# Tube_Screamer_Schematic.net
KiCad netlist of a schematic drawn in EAGLE
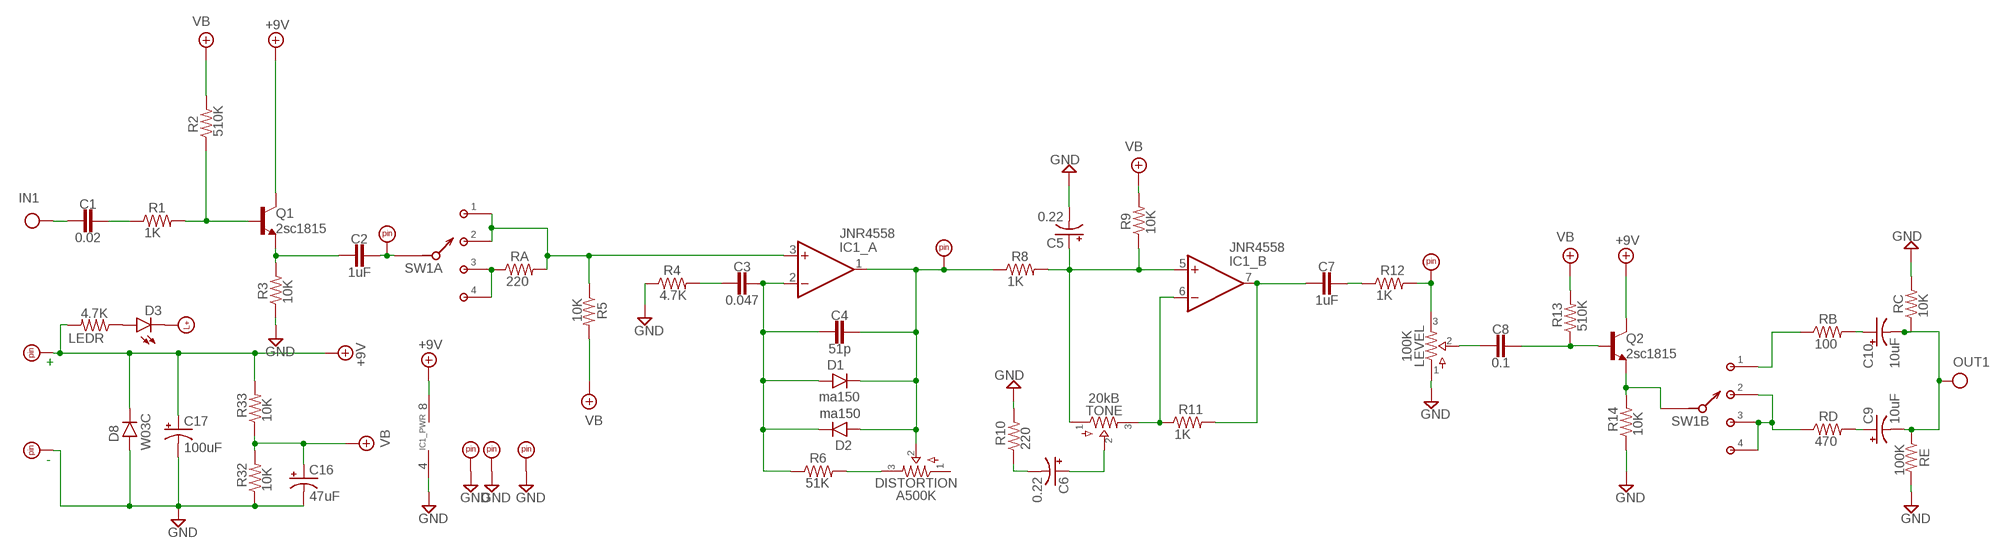
[diagram p0: schematic, sheet 1]

(export (version "E")
  (design (tool "Eeschema 10.0.6"))
  (components
    (comp (ref "C1")
      (value "0.02")
      (footprint "eagle-import:0.2_.MED")
      (libsource (lib "eagle-import") (part "CAP.3"))
    )
    (comp (ref "C2")
      (value "1uF")
      (footprint "eagle-import:0.2_.LRG")
      (libsource (lib "eagle-import") (part "CAP.4"))
    )
    (comp (ref "C3")
      (value "0.047")
      (footprint "eagle-import:0.2_.MED")
      (libsource (lib "eagle-import") (part "CAP.3"))
    )
    (comp (ref "C4")
      (value "51p")
      (footprint "eagle-import:0.2_.MED")
      (libsource (lib "eagle-import") (part "CAP.3"))
    )
    (comp (ref "C5")
      (value "0.22")
      (footprint "eagle-import:050_020_1")
      (libsource (lib "eagle-import") (part "0501"))
    )
    (comp (ref "C6")
      (value "0.22")
      (footprint "eagle-import:050_020_1")
      (libsource (lib "eagle-import") (part "0501"))
    )
    (comp (ref "C7")
      (value "1uF")
      (footprint "eagle-import:0.2_.LRG")
      (libsource (lib "eagle-import") (part "CAP.4"))
    )
    (comp (ref "C8")
      (value "0.1")
      (footprint "eagle-import:0.2_.MED")
      (libsource (lib "eagle-import") (part "CAP.3"))
    )
    (comp (ref "C9")
      (value "10uF")
      (footprint "eagle-import:050_020_1")
      (libsource (lib "eagle-import") (part "0501"))
    )
    (comp (ref "C10")
      (value "10uF")
      (footprint "eagle-import:050_020_1")
      (libsource (lib "eagle-import") (part "0501"))
    )
    (comp (ref "C16")
      (value "47uF")
      (footprint "eagle-import:050_020_1")
      (libsource (lib "eagle-import") (part "0501"))
    )
    (comp (ref "C17")
      (value "100uF")
      (footprint "eagle-import:050_020_1")
      (libsource (lib "eagle-import") (part "0501"))
    )
    (comp (ref "D1")
      (value "ma150")
      (footprint "eagle-import:DO41-3")
      (libsource (lib "eagle-import") (part "DO41.3"))
    )
    (comp (ref "D2")
      (value "ma150")
      (footprint "eagle-import:DO41-3")
      (libsource (lib "eagle-import") (part "DO41.3"))
    )
    (comp (ref "D3")
      (value "LED3MM")
      (footprint "eagle-import:LED3MM")
      (libsource (lib "eagle-import") (part "LED3MM"))
    )
    (comp (ref "D8")
      (value "W03C")
      (footprint "eagle-import:DO35-3")
      (libsource (lib "eagle-import") (part "DO35.3"))
    )
    (comp (ref "DISTORTION")
      (value "A500K")
      (footprint "eagle-import:16MM_B.MOUNT")
      (libsource (lib "eagle-import") (part "16MM.1"))
    )
    (comp (ref "IC1")
      (value "JNR4558")
      (footprint "eagle-import:DIL08")
      (libsource (lib "eagle-import") (part "DUALTH"))
    )
    (comp (ref "IN1")
      (value "IN")
      (footprint "eagle-import:SQUARE")
      (libsource (lib "eagle-import") (part "IN"))
    )
    (comp (ref "LEDR")
      (value "4.7K")
      (footprint "eagle-import:R0207_3")
      (libsource (lib "eagle-import") (part "RESISTORS.3B"))
    )
    (comp (ref "LEVEL")
      (value "100K")
      (footprint "eagle-import:16MM_B.MOUNT")
      (libsource (lib "eagle-import") (part "16MM.1"))
    )
    (comp (ref "OUT1")
      (value "OUT")
      (footprint "eagle-import:SQUARE")
      (libsource (lib "eagle-import") (part "OUT"))
    )
    (comp (ref "Q1")
      (value "2sc1815")
      (footprint "eagle-import:TO92")
      (libsource (lib "eagle-import") (part "2SC945"))
    )
    (comp (ref "Q2")
      (value "2sc1815")
      (footprint "eagle-import:TO92")
      (libsource (lib "eagle-import") (part "2SC945"))
    )
    (comp (ref "R1")
      (value "1K")
      (footprint "eagle-import:R0207_3")
      (libsource (lib "eagle-import") (part "RESISTORS.3B"))
    )
    (comp (ref "R2")
      (value "510K")
      (footprint "eagle-import:R0207_3")
      (libsource (lib "eagle-import") (part "RESISTORS.3B"))
    )
    (comp (ref "R3")
      (value "10K")
      (footprint "eagle-import:R0207_3")
      (libsource (lib "eagle-import") (part "RESISTORS.3B"))
    )
    (comp (ref "R4")
      (value "4.7K")
      (footprint "eagle-import:R0207_3")
      (libsource (lib "eagle-import") (part "RESISTORS.3B"))
    )
    (comp (ref "R5")
      (value "10K")
      (footprint "eagle-import:R0207_3")
      (libsource (lib "eagle-import") (part "RESISTORS.3B"))
    )
    (comp (ref "R6")
      (value "51K")
      (footprint "eagle-import:R0207_3")
      (libsource (lib "eagle-import") (part "RESISTORS.3B"))
    )
    (comp (ref "R8")
      (value "1K")
      (footprint "eagle-import:R0207_3")
      (libsource (lib "eagle-import") (part "RESISTORS.3B"))
    )
    (comp (ref "R9")
      (value "10K")
      (footprint "eagle-import:R0207_3")
      (libsource (lib "eagle-import") (part "RESISTORS.3B"))
    )
    (comp (ref "R10")
      (value "220")
      (footprint "eagle-import:R0207_3")
      (libsource (lib "eagle-import") (part "RESISTORS.3B"))
    )
    (comp (ref "R11")
      (value "1K")
      (footprint "eagle-import:R0207_3")
      (libsource (lib "eagle-import") (part "RESISTORS.3B"))
    )
    (comp (ref "R12")
      (value "1K")
      (footprint "eagle-import:R0207_3")
      (libsource (lib "eagle-import") (part "RESISTORS.3B"))
    )
    (comp (ref "R13")
      (value "510K")
      (footprint "eagle-import:R0207_3")
      (libsource (lib "eagle-import") (part "RESISTORS.3B"))
    )
    (comp (ref "R14")
      (value "10K")
      (footprint "eagle-import:R0207_3")
      (libsource (lib "eagle-import") (part "RESISTORS.3B"))
    )
    (comp (ref "R32")
      (value "10K")
      (footprint "eagle-import:R0207_3")
      (libsource (lib "eagle-import") (part "RESISTORS.3B"))
    )
    (comp (ref "R33")
      (value "10K")
      (footprint "eagle-import:R0207_3")
      (libsource (lib "eagle-import") (part "RESISTORS.3B"))
    )
    (comp (ref "RA")
      (value "220")
      (footprint "eagle-import:R0207_3")
      (libsource (lib "eagle-import") (part "RESISTORS.3B"))
    )
    (comp (ref "RB")
      (value "100")
      (footprint "eagle-import:R0207_3")
      (libsource (lib "eagle-import") (part "RESISTORS.3B"))
    )
    (comp (ref "RC")
      (value "10K")
      (footprint "eagle-import:R0207_3")
      (libsource (lib "eagle-import") (part "RESISTORS.3B"))
    )
    (comp (ref "RD")
      (value "470")
      (footprint "eagle-import:R0207_3")
      (libsource (lib "eagle-import") (part "RESISTORS.3B"))
    )
    (comp (ref "RE")
      (value "100K")
      (footprint "eagle-import:R0207_3")
      (libsource (lib "eagle-import") (part "RESISTORS.3B"))
    )
    (comp (ref "SW1")
      (value "2P4TMINIROTARY")
      (footprint "eagle-import:2P4T.MINI")
      (libsource (lib "eagle-import") (part "2P4TMINIROTARY"))
    )
    (comp (ref "TONE")
      (value "20kB")
      (footprint "eagle-import:16MM_B.MOUNT")
      (libsource (lib "eagle-import") (part "16MM.1"))
    )
    (comp (ref "U$1")
      (value "PADS.RND_NL")
      (footprint "eagle-import:PAD2")
      (libsource (lib "eagle-import") (part "PADS.RND_NL"))
    )
    (comp (ref "U$2")
      (value "PADS.RND_NL")
      (footprint "eagle-import:PAD2")
      (libsource (lib "eagle-import") (part "PADS.RND_NL"))
    )
    (comp (ref "U$3")
      (value "PADS.RND_NL")
      (footprint "eagle-import:PAD2")
      (libsource (lib "eagle-import") (part "PADS.RND_NL"))
    )
    (comp (ref "U$4")
      (value "PADS.RND_NL")
      (footprint "eagle-import:PAD2")
      (libsource (lib "eagle-import") (part "PADS.RND_NL"))
    )
    (comp (ref "U$5")
      (value "PADS.RND_NL")
      (footprint "eagle-import:PAD2")
      (libsource (lib "eagle-import") (part "PADS.RND_NL"))
    )
    (comp (ref "U$6")
      (value "PADS.RND_NL")
      (footprint "eagle-import:PAD2")
      (libsource (lib "eagle-import") (part "PADS.RND_NL"))
    )
    (comp (ref "U$7")
      (value "LED+")
      (footprint "eagle-import:SQUARE")
      (libsource (lib "eagle-import") (part "LED+"))
    )
    (comp (ref "U$8")
      (value "PADS.RND_NL")
      (footprint "eagle-import:PAD2")
      (libsource (lib "eagle-import") (part "PADS.RND_NL"))
    )
    (comp (ref "U$9")
      (value "PADS.RND_NL")
      (footprint "eagle-import:PAD2")
      (libsource (lib "eagle-import") (part "PADS.RND_NL"))
    )
  )
  (nets
    (net (code "1") (name "+9V") (class "Default")
      (node (ref "C17") (pin "+") (pinfunction "+_+") (pintype "passive"))
      (node (ref "D8") (pin "C") (pinfunction "C_C") (pintype "passive"))
      (node (ref "IC1") (pin "8") (pinfunction "V+_8") (pintype "power_in"))
      (node (ref "LEDR") (pin "2") (pinfunction "2_2") (pintype "passive"))
      (node (ref "Q1") (pin "2") (pinfunction "C_2") (pintype "passive"))
      (node (ref "Q2") (pin "2") (pinfunction "C_2") (pintype "passive"))
      (node (ref "R33") (pin "2") (pinfunction "2_2") (pintype "passive"))
      (node (ref "U$1") (pin "P$1") (pinfunction "P$1_P$1") (pintype "bidirectional"))
    )
    (net (code "2") (name "GND") (class "Default")
      (node (ref "C16") (pin "-") (pinfunction "-_-") (pintype "passive"))
      (node (ref "C17") (pin "-") (pinfunction "-_-") (pintype "passive"))
      (node (ref "C5") (pin "-") (pinfunction "-_-") (pintype "passive"))
      (node (ref "D8") (pin "A") (pinfunction "A_A") (pintype "passive"))
      (node (ref "IC1") (pin "4") (pinfunction "V-_4") (pintype "power_in"))
      (node (ref "LEVEL") (pin "1") (pinfunction "1_1") (pintype "passive"))
      (node (ref "R10") (pin "2") (pinfunction "2_2") (pintype "passive"))
      (node (ref "R14") (pin "1") (pinfunction "1_1") (pintype "passive"))
      (node (ref "R3") (pin "1") (pinfunction "1_1") (pintype "passive"))
      (node (ref "R32") (pin "1") (pinfunction "1_1") (pintype "passive"))
      (node (ref "R4") (pin "1") (pinfunction "1_1") (pintype "passive"))
      (node (ref "RC") (pin "2") (pinfunction "2_2") (pintype "passive"))
      (node (ref "RE") (pin "2") (pinfunction "2_2") (pintype "passive"))
      (node (ref "U$2") (pin "P$1") (pinfunction "P$1_P$1") (pintype "bidirectional"))
      (node (ref "U$3") (pin "P$1") (pinfunction "P$1_P$1") (pintype "bidirectional"))
      (node (ref "U$4") (pin "P$1") (pinfunction "P$1_P$1") (pintype "bidirectional"))
      (node (ref "U$5") (pin "P$1") (pinfunction "P$1_P$1") (pintype "bidirectional"))
    )
    (net (code "3") (name "IN") (class "Default")
      (node (ref "C1") (pin "2") (pinfunction "2_2") (pintype "passive"))
      (node (ref "IN1") (pin "1") (pinfunction "IN_1") (pintype "power_in"))
    )
    (net (code "4") (name "Net-(C1-Pad1)") (class "Default")
      (node (ref "C1") (pin "1") (pinfunction "1_1") (pintype "passive"))
      (node (ref "R1") (pin "1") (pinfunction "1_1") (pintype "passive"))
    )
    (net (code "5") (name "Net-(C2-Pad1)") (class "Default")
      (node (ref "C2") (pin "1") (pinfunction "1_1") (pintype "passive"))
      (node (ref "SW1") (pin "A") (pinfunction "A_A") (pintype "bidirectional"))
      (node (ref "U$6") (pin "P$1") (pinfunction "P$1_P$1") (pintype "bidirectional"))
    )
    (net (code "6") (name "Net-(C3-Pad2)") (class "Default")
      (node (ref "C3") (pin "2") (pinfunction "2_2") (pintype "passive"))
      (node (ref "R4") (pin "2") (pinfunction "2_2") (pintype "passive"))
    )
    (net (code "7") (name "Net-(C6-Pad+)") (class "Default")
      (node (ref "C6") (pin "+") (pinfunction "+_+") (pintype "passive"))
      (node (ref "TONE") (pin "2") (pinfunction "2_2") (pintype "passive"))
    )
    (net (code "8") (name "Net-(C6-Pad-)") (class "Default")
      (node (ref "C6") (pin "-") (pinfunction "-_-") (pintype "passive"))
      (node (ref "R10") (pin "1") (pinfunction "1_1") (pintype "passive"))
    )
    (net (code "9") (name "Net-(C7-Pad1)") (class "Default")
      (node (ref "C7") (pin "1") (pinfunction "1_1") (pintype "passive"))
      (node (ref "R12") (pin "1") (pinfunction "1_1") (pintype "passive"))
    )
    (net (code "10") (name "Net-(C8-Pad2)") (class "Default")
      (node (ref "C8") (pin "2") (pinfunction "2_2") (pintype "passive"))
      (node (ref "LEVEL") (pin "2") (pinfunction "2_2") (pintype "passive"))
    )
    (net (code "11") (name "Net-(C9-Pad+)") (class "Default")
      (node (ref "C9") (pin "+") (pinfunction "+_+") (pintype "passive"))
      (node (ref "RD") (pin "2") (pinfunction "2_2") (pintype "passive"))
    )
    (net (code "12") (name "Net-(C10-Pad+)") (class "Default")
      (node (ref "C10") (pin "+") (pinfunction "+_+") (pintype "passive"))
      (node (ref "RB") (pin "2") (pinfunction "2_2") (pintype "passive"))
    )
    (net (code "13") (name "Net-(D3-C)") (class "Default")
      (node (ref "D3") (pin "K") (pinfunction "C_K") (pintype "passive"))
      (node (ref "U$7") (pin "1") (pinfunction "P$1_1") (pintype "bidirectional"))
    )
    (net (code "14") (name "Net-(D3-PadA)") (class "Default")
      (node (ref "D3") (pin "A") (pinfunction "A_A") (pintype "passive"))
      (node (ref "LEDR") (pin "1") (pinfunction "1_1") (pintype "passive"))
    )
    (net (code "15") (name "Net-(DISTORTION-Pad3)") (class "Default")
      (node (ref "DISTORTION") (pin "3") (pinfunction "3_3") (pintype "passive"))
      (node (ref "R6") (pin "2") (pinfunction "2_2") (pintype "passive"))
    )
    (net (code "16") (name "Net-(IC1A-+IN)") (class "Default")
      (node (ref "IC1") (pin "3") (pinfunction "+IN_3") (pintype "input"))
      (node (ref "R5") (pin "1") (pinfunction "1_1") (pintype "passive"))
      (node (ref "RA") (pin "2") (pinfunction "2_2") (pintype "passive"))
      (node (ref "SW1") (pin "A1") (pinfunction "1_A1") (pintype "bidirectional"))
      (node (ref "SW1") (pin "A2") (pinfunction "2_A2") (pintype "bidirectional"))
    )
    (net (code "17") (name "Net-(IC1A--IN)") (class "Default")
      (node (ref "C3") (pin "1") (pinfunction "1_1") (pintype "passive"))
      (node (ref "C4") (pin "2") (pinfunction "2_2") (pintype "passive"))
      (node (ref "D1") (pin "A") (pinfunction "A_A") (pintype "passive"))
      (node (ref "D2") (pin "C") (pinfunction "C_C") (pintype "passive"))
      (node (ref "IC1") (pin "2") (pinfunction "-IN_2") (pintype "input"))
      (node (ref "R6") (pin "1") (pinfunction "1_1") (pintype "passive"))
    )
    (net (code "18") (name "Net-(IC1A-OUT)") (class "Default")
      (node (ref "C4") (pin "1") (pinfunction "1_1") (pintype "passive"))
      (node (ref "D1") (pin "C") (pinfunction "C_C") (pintype "passive"))
      (node (ref "D2") (pin "A") (pinfunction "A_A") (pintype "passive"))
      (node (ref "DISTORTION") (pin "2") (pinfunction "2_2") (pintype "passive"))
      (node (ref "IC1") (pin "1") (pinfunction "OUT_1") (pintype "output"))
      (node (ref "R8") (pin "1") (pinfunction "1_1") (pintype "passive"))
      (node (ref "U$8") (pin "P$1") (pinfunction "P$1_P$1") (pintype "bidirectional"))
    )
    (net (code "19") (name "Net-(IC1B-+IN)") (class "Default")
      (node (ref "C5") (pin "+") (pinfunction "+_+") (pintype "passive"))
      (node (ref "IC1") (pin "5") (pinfunction "+IN_5") (pintype "input"))
      (node (ref "R8") (pin "2") (pinfunction "2_2") (pintype "passive"))
      (node (ref "R9") (pin "1") (pinfunction "1_1") (pintype "passive"))
      (node (ref "TONE") (pin "1") (pinfunction "1_1") (pintype "passive"))
    )
    (net (code "20") (name "Net-(IC1B--IN)") (class "Default")
      (node (ref "IC1") (pin "6") (pinfunction "-IN_6") (pintype "input"))
      (node (ref "R11") (pin "1") (pinfunction "1_1") (pintype "passive"))
      (node (ref "TONE") (pin "3") (pinfunction "3_3") (pintype "passive"))
    )
    (net (code "21") (name "Net-(IC1B-OUT)") (class "Default")
      (node (ref "C7") (pin "2") (pinfunction "2_2") (pintype "passive"))
      (node (ref "IC1") (pin "7") (pinfunction "OUT_7") (pintype "output"))
      (node (ref "R11") (pin "2") (pinfunction "2_2") (pintype "passive"))
    )
    (net (code "22") (name "Net-(LEVEL-Pad3)") (class "Default")
      (node (ref "LEVEL") (pin "3") (pinfunction "3_3") (pintype "passive"))
      (node (ref "R12") (pin "2") (pinfunction "2_2") (pintype "passive"))
      (node (ref "U$9") (pin "P$1") (pinfunction "P$1_P$1") (pintype "bidirectional"))
    )
    (net (code "23") (name "Net-(Q1-B)") (class "Default")
      (node (ref "Q1") (pin "1") (pinfunction "B_1") (pintype "passive"))
      (node (ref "R1") (pin "2") (pinfunction "2_2") (pintype "passive"))
      (node (ref "R2") (pin "1") (pinfunction "1_1") (pintype "passive"))
    )
    (net (code "24") (name "Net-(Q1-E)") (class "Default")
      (node (ref "C2") (pin "2") (pinfunction "2_2") (pintype "passive"))
      (node (ref "Q1") (pin "3") (pinfunction "E_3") (pintype "passive"))
      (node (ref "R3") (pin "2") (pinfunction "2_2") (pintype "passive"))
    )
    (net (code "25") (name "Net-(Q2-B)") (class "Default")
      (node (ref "C8") (pin "1") (pinfunction "1_1") (pintype "passive"))
      (node (ref "Q2") (pin "1") (pinfunction "B_1") (pintype "passive"))
      (node (ref "R13") (pin "1") (pinfunction "1_1") (pintype "passive"))
    )
    (net (code "26") (name "Net-(Q2-E)") (class "Default")
      (node (ref "Q2") (pin "3") (pinfunction "E_3") (pintype "passive"))
      (node (ref "R14") (pin "2") (pinfunction "2_2") (pintype "passive"))
      (node (ref "SW1") (pin "B") (pinfunction "A_B") (pintype "bidirectional"))
    )
    (net (code "27") (name "Net-(SW1A-3)") (class "Default")
      (node (ref "RA") (pin "1") (pinfunction "1_1") (pintype "passive"))
      (node (ref "SW1") (pin "A3") (pinfunction "3_A3") (pintype "bidirectional"))
      (node (ref "SW1") (pin "A4") (pinfunction "4_A4") (pintype "bidirectional"))
    )
    (net (code "28") (name "Net-(SW1B-1)") (class "Default")
      (node (ref "RB") (pin "1") (pinfunction "1_1") (pintype "passive"))
      (node (ref "SW1") (pin "B1") (pinfunction "1_B1") (pintype "bidirectional"))
    )
    (net (code "29") (name "Net-(SW1B-2)") (class "Default")
      (node (ref "RD") (pin "1") (pinfunction "1_1") (pintype "passive"))
      (node (ref "SW1") (pin "B2") (pinfunction "2_B2") (pintype "bidirectional"))
      (node (ref "SW1") (pin "B3") (pinfunction "3_B3") (pintype "bidirectional"))
      (node (ref "SW1") (pin "B4") (pinfunction "4_B4") (pintype "bidirectional"))
    )
    (net (code "30") (name "OUT") (class "Default")
      (node (ref "C10") (pin "-") (pinfunction "-_-") (pintype "passive"))
      (node (ref "C9") (pin "-") (pinfunction "-_-") (pintype "passive"))
      (node (ref "OUT1") (pin "1") (pinfunction "OUT_1") (pintype "power_in"))
      (node (ref "RC") (pin "1") (pinfunction "1_1") (pintype "passive"))
      (node (ref "RE") (pin "1") (pinfunction "1_1") (pintype "passive"))
    )
    (net (code "31") (name "VB") (class "Default")
      (node (ref "C16") (pin "+") (pinfunction "+_+") (pintype "passive"))
      (node (ref "R13") (pin "2") (pinfunction "2_2") (pintype "passive"))
      (node (ref "R2") (pin "2") (pinfunction "2_2") (pintype "passive"))
      (node (ref "R32") (pin "2") (pinfunction "2_2") (pintype "passive"))
      (node (ref "R33") (pin "1") (pinfunction "1_1") (pintype "passive"))
      (node (ref "R5") (pin "2") (pinfunction "2_2") (pintype "passive"))
      (node (ref "R9") (pin "2") (pinfunction "2_2") (pintype "passive"))
    )
    (net (code "32") (name "unconnected-(DISTORTION-Pad1)") (class "Default")
      (node (ref "DISTORTION") (pin "1") (pinfunction "1_1") (pintype "passive"))
    )
  )
)
